# Calimotion_7.net
KiCad netlist of a schematic drawn in Altium Designer
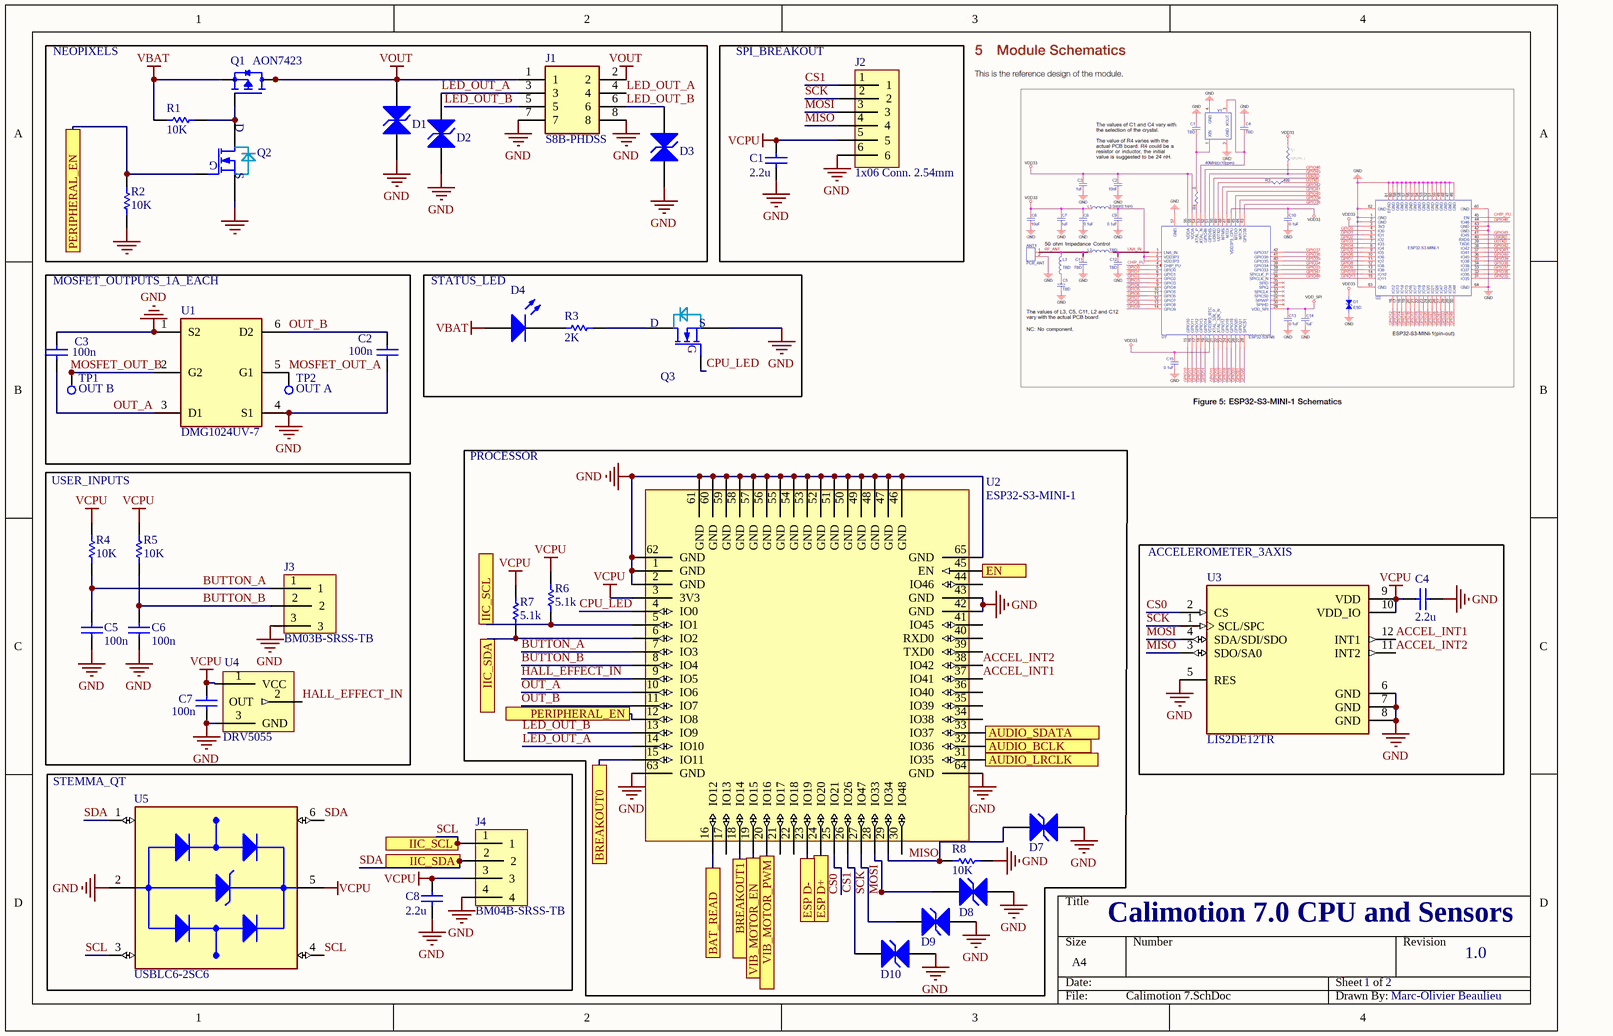
[diagram p0: Calimotion 7.SchDoc]

(export (version "E")
  (design (tool "Eeschema 10.0.6"))
  (components
    (comp (ref "C1")
      (value "2.2u")
      (footprint "CAP 0402_1005")
      (description "Capacitor")
      (libsource (lib "Simulation Generic Components") (part "Capacitor"))
    )
    (comp (ref "C2")
      (value "100n")
      (footprint "CAP 0402_1005")
      (description "Capacitor")
      (libsource (lib "Simulation Generic Components") (part "Capacitor"))
    )
    (comp (ref "C3")
      (value "100n")
      (footprint "CAP 0402_1005")
      (description "Capacitor")
      (libsource (lib "Simulation Generic Components") (part "Capacitor"))
    )
    (comp (ref "C4")
      (value "2.2u")
      (footprint "CAP 0402_1005")
      (description "Capacitor")
      (libsource (lib "Simulation Generic Components") (part "Capacitor"))
    )
    (comp (ref "C5")
      (value "100n")
      (footprint "CAP 0402_1005")
      (description "Capacitor")
      (libsource (lib "Simulation Generic Components") (part "Capacitor"))
    )
    (comp (ref "C6")
      (value "100n")
      (footprint "CAP 0402_1005")
      (description "Capacitor")
      (libsource (lib "Simulation Generic Components") (part "Capacitor"))
    )
    (comp (ref "C7")
      (value "100n")
      (footprint "CAP 0402_1005")
      (description "Capacitor")
      (libsource (lib "Simulation Generic Components") (part "Capacitor"))
    )
    (comp (ref "C8")
      (value "2.2u")
      (footprint "CAP 0402_1005")
      (description "Capacitor")
      (libsource (lib "Simulation Generic Components") (part "Capacitor"))
    )
    (comp (ref "D1")
      (value "TVS")
      (footprint "SOD-923")
      (description "TVS 5.8V 50W SOD523")
      (fields (field (name "VOLTAGE") "5.8V") (field (name "MANUFACTURER") "On Semiconductor"))
      (libsource (lib "ALTIUM_Diode") (part "DIO_1027"))
    )
    (comp (ref "D2")
      (value "TVS")
      (footprint "SOD-923")
      (description "TVS 5.8V 50W SOD523")
      (fields (field (name "VOLTAGE") "5.8V") (field (name "MANUFACTURER") "On Semiconductor"))
      (libsource (lib "ALTIUM_Diode") (part "DIO_1027"))
    )
    (comp (ref "D3")
      (value "TVS")
      (footprint "SOD-923")
      (description "TVS 5.8V 50W SOD523")
      (fields (field (name "VOLTAGE") "5.8V") (field (name "MANUFACTURER") "On Semiconductor"))
      (libsource (lib "ALTIUM_Diode") (part "DIO_1027"))
    )
    (comp (ref "D4")
      (value "Light-Emitting Diode")
      (footprint "LEDSC160X80X70L45N")
      (libsource (lib "Simulation Generic Components") (part "LED"))
    )
    (comp (ref "D7")
      (value "TVS")
      (footprint "SOD-923")
      (description "TVS 5.8V 50W SOD523")
      (fields (field (name "VOLTAGE") "5.8V") (field (name "MANUFACTURER") "On Semiconductor"))
      (libsource (lib "ALTIUM_Diode") (part "DIO_1027"))
    )
    (comp (ref "D8")
      (value "TVS")
      (footprint "SOD-923")
      (description "TVS 5.8V 50W SOD523")
      (fields (field (name "VOLTAGE") "5.8V") (field (name "MANUFACTURER") "On Semiconductor"))
      (libsource (lib "ALTIUM_Diode") (part "DIO_1027"))
    )
    (comp (ref "D9")
      (value "TVS")
      (footprint "SOD-923")
      (description "TVS 5.8V 50W SOD523")
      (fields (field (name "VOLTAGE") "5.8V") (field (name "MANUFACTURER") "On Semiconductor"))
      (libsource (lib "ALTIUM_Diode") (part "DIO_1027"))
    )
    (comp (ref "D10")
      (value "TVS")
      (footprint "SOD-923")
      (description "TVS 5.8V 50W SOD523")
      (fields (field (name "VOLTAGE") "5.8V") (field (name "MANUFACTURER") "On Semiconductor"))
      (libsource (lib "ALTIUM_Diode") (part "DIO_1027"))
    )
    (comp (ref "J1")
      (value "S8B-PHDSS")
      (footprint "JST_S8B-PHDSS")
      (description "Connector Header Through Hole, Right Angle 8 position 0.079 _2.00mm_")
      (fields (field (name "MF") "JST Sales"))
      (libsource (lib "Importred_Components") (part "S8B-PHDSS"))
    )
    (comp (ref "J2")
      (value "1x06 Conn. 2.54mm")
      (footprint "1x06 Conn. 2.54mm")
      (libsource (lib "Importred_Components") (part "1x06 Conn. 2.54mm"))
    )
    (comp (ref "J3")
      (value "BM03B-SRSS-TB")
      (footprint "BM03B-SRSS-TB")
      (description "Connector Header Surface Mount 3 position 0.039\" (1.00mm)")
      (libsource (lib "Importred_Components") (part "BM03B-SRSS-TB"))
    )
    (comp (ref "J4")
      (value "BM04B-SRSS-TB")
      (footprint "BM04B-SRSS-TB")
      (description "Connector Header Surface Mount 4 position 0.039\" (1.00mm)")
      (libsource (lib "Importred_Components") (part "BM04B-SRSS-TB"))
    )
    (comp (ref "Q1")
      (value "AON7423")
      (footprint "TRANS_8PDFN")
      (description "-30, -64, Single P-Channel")
      (fields (field (name "MF") "Taiwan Semiconductor Corporation") (field (name "MP") "TSM085P03CV RGG"))
      (libsource (lib "Importred_Components") (part "TSM085P03CV_RGG"))
    )
    (comp (ref "Q2")
      (value "MOSFET-N")
      (footprint "TRANS_SOT-416")
      (description "20 V, 238 mA, Single, N−Channel, Gate ESD Protection, SC−75")
      (fields (field (name "VOLTAGE") "20V") (field (name "MANUFACTURER") "OnSemi"))
      (libsource (lib "ALTIUM_Transistor") (part "TRANS_1070"))
    )
    (comp (ref "Q3")
      (value "MOSFET-N")
      (footprint "TRANS_SOT-416")
      (description "MOSFET N-CH 20V 915MA SOT-416")
      (fields (field (name "VOLTAGE") "20V") (field (name "MANUFACTURER") "ON Semiconductor"))
      (libsource (lib "ALTIUM_Transistor") (part "TRANS_1057"))
    )
    (comp (ref "R1")
      (value "10K")
      (footprint "RES 0402_1005 RF")
      (description "Resistor")
      (libsource (lib "Simulation Generic Components") (part "Resistor"))
    )
    (comp (ref "R2")
      (value "10K")
      (footprint "RES 0402_1005 RF")
      (description "Resistor")
      (libsource (lib "Simulation Generic Components") (part "Resistor"))
    )
    (comp (ref "R3")
      (value "2K")
      (footprint "RES 0402_1005 RF")
      (description "Resistor")
      (libsource (lib "Simulation Generic Components") (part "Resistor"))
    )
    (comp (ref "R4")
      (value "10K")
      (footprint "RES 0402_1005 RF")
      (description "Resistor")
      (libsource (lib "Simulation Generic Components") (part "Resistor"))
    )
    (comp (ref "R5")
      (value "10K")
      (footprint "RES 0402_1005 RF")
      (description "Resistor")
      (libsource (lib "Simulation Generic Components") (part "Resistor"))
    )
    (comp (ref "R6")
      (value "5.1k")
      (footprint "RES 0402_1005 RF")
      (description "Resistor")
      (libsource (lib "Simulation Generic Components") (part "Resistor"))
    )
    (comp (ref "R7")
      (value "5.1k")
      (footprint "RES 0402_1005 RF")
      (description "Resistor")
      (libsource (lib "Simulation Generic Components") (part "Resistor"))
    )
    (comp (ref "R8")
      (value "10K")
      (footprint "RES 0402_1005 RF")
      (description "Resistor")
      (libsource (lib "Simulation Generic Components") (part "Resistor"))
    )
    (comp (ref "TP1")
      (value "OUT B")
      (footprint "THT-Test_Point")
      (libsource (lib "Celestial Library") (part "Test Point"))
    )
    (comp (ref "TP2")
      (value "OUT A")
      (footprint "THT-Test_Point")
      (libsource (lib "Celestial Library") (part "Test Point"))
    )
    (comp (ref "U1")
      (value "DMG1024UV-7")
      (footprint "74LVC2G17GW,125")
      (description "Mosfet Array 2 N-Channel _Dual_ 20V 1.38A 530mW Surface Mount SOT-563")
      (fields (field (name "MF") "Diodes Inc."))
      (libsource (lib "Importred_Components") (part "DMG1024UV-7"))
    )
    (comp (ref "U2")
      (value "ESP32-S3-MINI-1")
      (footprint "ESP32-S3-MINI-1")
      (description "Bluetooth, WiFi 802.11b/g/n, Bluetooth v5.0 Transceiver Module 2.4GHz PCB Trace Surface Mount")
      (libsource (lib "ESP32_library") (part "ESP32-S3-MINI-1"))
    )
    (comp (ref "U3")
      (value "LIS2DE12TR")
      (footprint "LIS2DE12TR_200X200X100-12N")
      (description "Accelerometer X, Y, Z Axis Â±2g, 4g, 8g, 16g 0.5Hz ~ 2.69kHz 12-LGA _2x2_")
      (fields (field (name "MF") "STMicroelectronics"))
      (libsource (lib "Importred_Components") (part "LIS2DE12TR"))
    )
    (comp (ref "U4")
      (value "DRV5055")
      (footprint "SOT23-3")
      (description "Hall Effect Sensor Single Axis SOT-23-3")
      (libsource (lib "Importred_Components") (part "DRV5055"))
    )
    (comp (ref "U5")
      (value "USBLC6-2SC6")
      (footprint "SOT95P280X145-6N")
      (description "17V Clamp 5A (8/20Âµs) Ipp Tvs Diode Surface Mount SOT-23-6")
      (fields (field (name "MF") "STMicroelectronics"))
      (libsource (lib "Importred_Components") (part "USBLC6-2SC6"))
    )
  )
  (nets
    (net (code "1") (name "/ACCEL_INT1") (class "Default")
      (node (ref "U2") (pin "37") (pinfunction "IO41_37") (pintype "bidirectional"))
      (node (ref "U3") (pin "12") (pinfunction "INT1_12") (pintype "output"))
    )
    (net (code "2") (name "/ACCEL_INT2") (class "Default")
      (node (ref "U2") (pin "38") (pinfunction "IO42_38") (pintype "bidirectional"))
      (node (ref "U3") (pin "11") (pinfunction "INT2_11") (pintype "output"))
    )
    (net (code "3") (name "/AUDIO_BCLK") (class "Default")
      (node (ref "U2") (pin "32") (pinfunction "IO36_32") (pintype "bidirectional"))
    )
    (net (code "4") (name "/AUDIO_LRCLK") (class "Default")
      (node (ref "U2") (pin "31") (pinfunction "IO35_31") (pintype "bidirectional"))
    )
    (net (code "5") (name "/AUDIO_SDATA") (class "Default")
      (node (ref "U2") (pin "33") (pinfunction "IO37_33") (pintype "bidirectional"))
    )
    (net (code "6") (name "/BAT_READ") (class "Default")
      (node (ref "U2") (pin "16") (pinfunction "IO12_16") (pintype "bidirectional"))
    )
    (net (code "7") (name "/BREAKOUT0") (class "Default")
      (node (ref "U2") (pin "15") (pinfunction "IO11_15") (pintype "bidirectional"))
    )
    (net (code "8") (name "/BREAKOUT1") (class "Default")
      (node (ref "U2") (pin "18") (pinfunction "IO14_18") (pintype "bidirectional"))
    )
    (net (code "9") (name "/BUTTON_A") (class "Default")
      (node (ref "C5") (pin "1") (pinfunction "1_1") (pintype "passive"))
      (node (ref "J3") (pin "1") (pinfunction "1_1") (pintype "passive"))
      (node (ref "R4") (pin "2") (pinfunction "2_2") (pintype "passive"))
      (node (ref "U2") (pin "7") (pinfunction "IO3_7") (pintype "bidirectional"))
    )
    (net (code "10") (name "/BUTTON_B") (class "Default")
      (node (ref "C6") (pin "1") (pinfunction "1_1") (pintype "passive"))
      (node (ref "J3") (pin "2") (pinfunction "2_2") (pintype "passive"))
      (node (ref "R5") (pin "2") (pinfunction "2_2") (pintype "passive"))
      (node (ref "U2") (pin "8") (pinfunction "IO4_8") (pintype "bidirectional"))
    )
    (net (code "11") (name "/CPU_LED") (class "Default")
      (node (ref "Q3") (pin "G") (pinfunction "G_G") (pintype "passive"))
      (node (ref "U2") (pin "4") (pinfunction "IO0_4") (pintype "bidirectional"))
    )
    (net (code "12") (name "/CS0") (class "Default")
      (node (ref "U2") (pin "25") (pinfunction "IO21_25") (pintype "bidirectional"))
      (node (ref "U3") (pin "2") (pinfunction "CS_2") (pintype "input"))
    )
    (net (code "13") (name "/CS1") (class "Default")
      (node (ref "D10") (pin "K") (pinfunction "K_K") (pintype "passive"))
      (node (ref "J2") (pin "1") (pinfunction "1_1") (pintype "passive"))
      (node (ref "U2") (pin "26") (pinfunction "IO26_26") (pintype "bidirectional"))
    )
    (net (code "14") (name "/EN") (class "Default")
      (node (ref "U2") (pin "45") (pinfunction "EN_45") (pintype "input"))
    )
    (net (code "15") (name "/ESP D+") (class "Default")
      (node (ref "U2") (pin "24") (pinfunction "IO20_24") (pintype "bidirectional"))
    )
    (net (code "16") (name "/ESP D-") (class "Default")
      (node (ref "U2") (pin "23") (pinfunction "IO19_23") (pintype "bidirectional"))
    )
    (net (code "17") (name "/HALL_EFFECT_IN") (class "Default")
      (node (ref "U2") (pin "9") (pinfunction "IO5_9") (pintype "bidirectional"))
      (node (ref "U4") (pin "2") (pinfunction "OUT_2") (pintype "output"))
    )
    (net (code "18") (name "/LED_OUT_A") (class "Default")
      (node (ref "D2") (pin "K") (pinfunction "K_K") (pintype "passive"))
      (node (ref "J1") (pin "3") (pinfunction "3_3") (pintype "passive"))
      (node (ref "J1") (pin "4") (pinfunction "4_4") (pintype "passive"))
      (node (ref "U2") (pin "14") (pinfunction "IO10_14") (pintype "bidirectional"))
    )
    (net (code "19") (name "/LED_OUT_B") (class "Default")
      (node (ref "D3") (pin "K") (pinfunction "K_K") (pintype "passive"))
      (node (ref "J1") (pin "5") (pinfunction "5_5") (pintype "passive"))
      (node (ref "J1") (pin "6") (pinfunction "6_6") (pintype "passive"))
    )
    (net (code "20") (name "/MISO") (class "Default")
      (node (ref "D7") (pin "K") (pinfunction "K_K") (pintype "passive"))
      (node (ref "J2") (pin "4") (pinfunction "4_4") (pintype "passive"))
      (node (ref "R8") (pin "2") (pinfunction "2_2") (pintype "passive"))
      (node (ref "U2") (pin "29") (pinfunction "IO34_29") (pintype "bidirectional"))
      (node (ref "U3") (pin "3") (pinfunction "SDO/SA0_3") (pintype "bidirectional"))
    )
    (net (code "21") (name "/MOSFET_OUT_A") (class "Default")
      (node (ref "TP2") (pin "1") (pinfunction "TP_1") (pintype "passive"))
      (node (ref "U1") (pin "5") (pinfunction "G1_5") (pintype "passive"))
    )
    (net (code "22") (name "/MOSFET_OUT_B") (class "Default")
      (node (ref "TP1") (pin "1") (pinfunction "TP_1") (pintype "passive"))
      (node (ref "U1") (pin "2") (pinfunction "G2_2") (pintype "passive"))
    )
    (net (code "23") (name "/MOSI") (class "Default")
      (node (ref "D8") (pin "K") (pinfunction "K_K") (pintype "passive"))
      (node (ref "J2") (pin "3") (pinfunction "3_3") (pintype "passive"))
      (node (ref "U2") (pin "28") (pinfunction "IO33_28") (pintype "bidirectional"))
      (node (ref "U3") (pin "4") (pinfunction "SDA/SDI/SDO_4") (pintype "bidirectional"))
    )
    (net (code "24") (name "/OUT_A") (class "Default")
      (node (ref "C3") (pin "1") (pinfunction "1_1") (pintype "passive"))
      (node (ref "U1") (pin "3") (pinfunction "D1_3") (pintype "passive"))
      (node (ref "U2") (pin "10") (pinfunction "IO6_10") (pintype "bidirectional"))
    )
    (net (code "25") (name "/OUT_B") (class "Default")
      (node (ref "C2") (pin "2") (pinfunction "2_2") (pintype "passive"))
      (node (ref "U1") (pin "6") (pinfunction "D2_6") (pintype "passive"))
      (node (ref "U2") (pin "11") (pinfunction "IO7_11") (pintype "bidirectional"))
    )
    (net (code "26") (name "/PERIPHERAL_EN") (class "Default")
      (node (ref "Q2") (pin "G") (pinfunction "G_G") (pintype "passive"))
      (node (ref "R2") (pin "1") (pinfunction "1_1") (pintype "passive"))
      (node (ref "U2") (pin "12") (pinfunction "IO8_12") (pintype "bidirectional"))
    )
    (net (code "27") (name "/SCK") (class "Default")
      (node (ref "D9") (pin "K") (pinfunction "K_K") (pintype "passive"))
      (node (ref "J2") (pin "2") (pinfunction "2_2") (pintype "passive"))
      (node (ref "U2") (pin "27") (pinfunction "IO47_27") (pintype "bidirectional"))
      (node (ref "U3") (pin "1") (pinfunction "SCL/SPC_1") (pintype "input"))
    )
    (net (code "28") (name "/SCL") (class "Default")
      (node (ref "J4") (pin "1") (pinfunction "1_1") (pintype "passive"))
      (node (ref "R6") (pin "1") (pinfunction "1_1") (pintype "passive"))
      (node (ref "U2") (pin "5") (pinfunction "IO1_5") (pintype "bidirectional"))
      (node (ref "U5") (pin "3") (pinfunction "I/O2_IN_3") (pintype "bidirectional"))
      (node (ref "U5") (pin "4") (pinfunction "I/O2_OUT_4") (pintype "bidirectional"))
    )
    (net (code "29") (name "/SDA") (class "Default")
      (node (ref "J4") (pin "2") (pinfunction "2_2") (pintype "passive"))
      (node (ref "R7") (pin "1") (pinfunction "1_1") (pintype "passive"))
      (node (ref "U2") (pin "6") (pinfunction "IO2_6") (pintype "bidirectional"))
      (node (ref "U5") (pin "1") (pinfunction "I/O1_IN_1") (pintype "bidirectional"))
      (node (ref "U5") (pin "6") (pinfunction "I/O1_OUT_6") (pintype "bidirectional"))
    )
    (net (code "30") (name "/VIB_MOTOR_EN") (class "Default")
      (node (ref "U2") (pin "19") (pinfunction "IO15_19") (pintype "bidirectional"))
    )
    (net (code "31") (name "/VIB_MOTOR_PWM") (class "Default")
      (node (ref "U2") (pin "20") (pinfunction "IO16_20") (pintype "bidirectional"))
    )
    (net (code "32") (name "GND") (class "Default")
      (node (ref "C1") (pin "1") (pinfunction "1_1") (pintype "passive"))
      (node (ref "C2") (pin "1") (pinfunction "1_1") (pintype "passive"))
      (node (ref "C3") (pin "2") (pinfunction "2_2") (pintype "passive"))
      (node (ref "C4") (pin "1") (pinfunction "1_1") (pintype "passive"))
      (node (ref "C5") (pin "2") (pinfunction "2_2") (pintype "passive"))
      (node (ref "C6") (pin "2") (pinfunction "2_2") (pintype "passive"))
      (node (ref "C7") (pin "1") (pinfunction "1_1") (pintype "passive"))
      (node (ref "C8") (pin "1") (pinfunction "1_1") (pintype "passive"))
      (node (ref "D1") (pin "A") (pinfunction "A_A") (pintype "passive"))
      (node (ref "D10") (pin "A") (pinfunction "A_A") (pintype "passive"))
      (node (ref "D2") (pin "A") (pinfunction "A_A") (pintype "passive"))
      (node (ref "D3") (pin "A") (pinfunction "A_A") (pintype "passive"))
      (node (ref "D7") (pin "A") (pinfunction "A_A") (pintype "passive"))
      (node (ref "D8") (pin "A") (pinfunction "A_A") (pintype "passive"))
      (node (ref "D9") (pin "A") (pinfunction "A_A") (pintype "passive"))
      (node (ref "J1") (pin "7") (pinfunction "7_7") (pintype "passive"))
      (node (ref "J1") (pin "8") (pinfunction "8_8") (pintype "passive"))
      (node (ref "J2") (pin "6") (pinfunction "6_6") (pintype "passive"))
      (node (ref "J3") (pin "3") (pinfunction "3_3") (pintype "passive"))
      (node (ref "J4") (pin "4") (pinfunction "4_4") (pintype "passive"))
      (node (ref "Q2") (pin "S") (pinfunction "S_S") (pintype "passive"))
      (node (ref "Q3") (pin "S") (pinfunction "S_S") (pintype "passive"))
      (node (ref "R2") (pin "2") (pinfunction "2_2") (pintype "passive"))
      (node (ref "R8") (pin "1") (pinfunction "1_1") (pintype "passive"))
      (node (ref "U1") (pin "1") (pinfunction "S2_1") (pintype "passive"))
      (node (ref "U1") (pin "4") (pinfunction "S1_4") (pintype "passive"))
      (node (ref "U2") (pin "1") (pinfunction "GND_1") (pintype "power_in"))
      (node (ref "U2") (pin "2") (pinfunction "GND_2") (pintype "power_in"))
      (node (ref "U2") (pin "42") (pinfunction "GND_42") (pintype "passive"))
      (node (ref "U2") (pin "43") (pinfunction "GND_43") (pintype "passive"))
      (node (ref "U2") (pin "46") (pinfunction "GND_46") (pintype "power_in"))
      (node (ref "U2") (pin "47") (pinfunction "GND_47") (pintype "power_in"))
      (node (ref "U2") (pin "48") (pinfunction "GND_48") (pintype "power_in"))
      (node (ref "U2") (pin "49") (pinfunction "GND_49") (pintype "power_in"))
      (node (ref "U2") (pin "50") (pinfunction "GND_50") (pintype "power_in"))
      (node (ref "U2") (pin "51") (pinfunction "GND_51") (pintype "power_in"))
      (node (ref "U2") (pin "52") (pinfunction "GND_52") (pintype "power_in"))
      (node (ref "U2") (pin "53") (pinfunction "GND_53") (pintype "power_in"))
      (node (ref "U2") (pin "54") (pinfunction "GND_54") (pintype "power_in"))
      (node (ref "U2") (pin "55") (pinfunction "GND_55") (pintype "power_in"))
      (node (ref "U2") (pin "56") (pinfunction "GND_56") (pintype "power_in"))
      (node (ref "U2") (pin "57") (pinfunction "GND_57") (pintype "power_in"))
      (node (ref "U2") (pin "58") (pinfunction "GND_58") (pintype "power_in"))
      (node (ref "U2") (pin "59") (pinfunction "GND_59") (pintype "power_in"))
      (node (ref "U2") (pin "60") (pinfunction "GND_60") (pintype "power_in"))
      (node (ref "U2") (pin "61") (pinfunction "GND_61") (pintype "passive"))
      (node (ref "U2") (pin "62") (pinfunction "GND_62") (pintype "power_in"))
      (node (ref "U2") (pin "63") (pinfunction "GND_63") (pintype "passive"))
      (node (ref "U2") (pin "64") (pinfunction "GND_64") (pintype "passive"))
      (node (ref "U2") (pin "65") (pinfunction "GND_65") (pintype "passive"))
      (node (ref "U3") (pin "5") (pinfunction "RES_5") (pintype "passive"))
      (node (ref "U3") (pin "6") (pinfunction "GND_6") (pintype "power_in"))
      (node (ref "U3") (pin "7") (pinfunction "GND_7") (pintype "power_in"))
      (node (ref "U3") (pin "8") (pinfunction "GND_8") (pintype "power_in"))
      (node (ref "U4") (pin "3") (pinfunction "GND_3") (pintype "power_in"))
      (node (ref "U5") (pin "2") (pinfunction "GND_2") (pintype "power_in"))
    )
    (net (code "33") (name "Net-(D4-K)") (class "Default")
      (node (ref "D4") (pin "2") (pinfunction "K_2") (pintype "passive"))
      (node (ref "R3") (pin "2") (pinfunction "2_2") (pintype "passive"))
    )
    (net (code "34") (name "Net-(Q1-G)") (class "Default")
      (node (ref "Q1") (pin "4") (pinfunction "G_4") (pintype "passive"))
      (node (ref "Q2") (pin "D") (pinfunction "D_D") (pintype "passive"))
      (node (ref "R1") (pin "1") (pinfunction "1_1") (pintype "passive"))
    )
    (net (code "35") (name "Net-(Q3-PadD)") (class "Default")
      (node (ref "Q3") (pin "D") (pinfunction "D_D") (pintype "passive"))
      (node (ref "R3") (pin "1") (pinfunction "1_1") (pintype "passive"))
    )
    (net (code "36") (name "VBAT") (class "Default")
      (node (ref "D4") (pin "1") (pinfunction "A_1") (pintype "passive"))
      (node (ref "Q1") (pin "5_8") (pinfunction "D_5_8") (pintype "passive"))
      (node (ref "R1") (pin "2") (pinfunction "2_2") (pintype "passive"))
    )
    (net (code "37") (name "VCPU") (class "Default")
      (node (ref "C1") (pin "2") (pinfunction "2_2") (pintype "passive"))
      (node (ref "C4") (pin "2") (pinfunction "2_2") (pintype "passive"))
      (node (ref "C7") (pin "2") (pinfunction "2_2") (pintype "passive"))
      (node (ref "C8") (pin "2") (pinfunction "2_2") (pintype "passive"))
      (node (ref "J2") (pin "5") (pinfunction "5_5") (pintype "passive"))
      (node (ref "J4") (pin "3") (pinfunction "3_3") (pintype "passive"))
      (node (ref "R4") (pin "1") (pinfunction "1_1") (pintype "passive"))
      (node (ref "R5") (pin "1") (pinfunction "1_1") (pintype "passive"))
      (node (ref "R6") (pin "2") (pinfunction "2_2") (pintype "passive"))
      (node (ref "R7") (pin "2") (pinfunction "2_2") (pintype "passive"))
      (node (ref "U2") (pin "3") (pinfunction "3V3_3") (pintype "power_in"))
      (node (ref "U3") (pin "10") (pinfunction "VDD_IO_10") (pintype "power_in"))
      (node (ref "U3") (pin "9") (pinfunction "VDD_9") (pintype "power_in"))
      (node (ref "U4") (pin "1") (pinfunction "VCC_1") (pintype "power_in"))
      (node (ref "U5") (pin "5") (pinfunction "VBUS_5") (pintype "power_in"))
    )
    (net (code "38") (name "VOUT") (class "Default")
      (node (ref "D1") (pin "K") (pinfunction "K_K") (pintype "passive"))
      (node (ref "J1") (pin "1") (pinfunction "1_1") (pintype "passive"))
      (node (ref "J1") (pin "2") (pinfunction "2_2") (pintype "passive"))
      (node (ref "Q1") (pin "1") (pinfunction "S_1") (pintype "passive"))
      (node (ref "Q1") (pin "2") (pinfunction "S_2") (pintype "passive"))
      (node (ref "Q1") (pin "3") (pinfunction "S_3") (pintype "passive"))
    )
    (net (code "39") (name "unconnected-(U2-IO9-Pad13)") (class "Default")
      (node (ref "U2") (pin "13") (pinfunction "IO9_13") (pintype "bidirectional"))
    )
    (net (code "40") (name "unconnected-(U2-IO13-Pad17)") (class "Default")
      (node (ref "U2") (pin "17") (pinfunction "IO13_17") (pintype "bidirectional"))
    )
    (net (code "41") (name "unconnected-(U2-IO17-Pad21)") (class "Default")
      (node (ref "U2") (pin "21") (pinfunction "IO17_21") (pintype "bidirectional"))
    )
    (net (code "42") (name "unconnected-(U2-IO18-Pad22)") (class "Default")
      (node (ref "U2") (pin "22") (pinfunction "IO18_22") (pintype "bidirectional"))
    )
    (net (code "43") (name "unconnected-(U2-IO38-Pad34)") (class "Default")
      (node (ref "U2") (pin "34") (pinfunction "IO38_34") (pintype "bidirectional"))
    )
    (net (code "44") (name "unconnected-(U2-IO39-Pad35)") (class "Default")
      (node (ref "U2") (pin "35") (pinfunction "IO39_35") (pintype "bidirectional"))
    )
    (net (code "45") (name "unconnected-(U2-IO40-Pad36)") (class "Default")
      (node (ref "U2") (pin "36") (pinfunction "IO40_36") (pintype "bidirectional"))
    )
    (net (code "46") (name "unconnected-(U2-IO45-Pad41)") (class "Default")
      (node (ref "U2") (pin "41") (pinfunction "IO45_41") (pintype "bidirectional"))
    )
    (net (code "47") (name "unconnected-(U2-IO46-Pad44)") (class "Default")
      (node (ref "U2") (pin "44") (pinfunction "IO46_44") (pintype "bidirectional"))
    )
    (net (code "48") (name "unconnected-(U2-IO48-Pad30)") (class "Default")
      (node (ref "U2") (pin "30") (pinfunction "IO48_30") (pintype "bidirectional"))
    )
    (net (code "49") (name "unconnected-(U2-RXD0-Pad40)") (class "Default")
      (node (ref "U2") (pin "40") (pinfunction "RXD0_40") (pintype "bidirectional"))
    )
    (net (code "50") (name "unconnected-(U2-TXD0-Pad39)") (class "Default")
      (node (ref "U2") (pin "39") (pinfunction "TXD0_39") (pintype "bidirectional"))
    )
  )
)
